# ST_LINK_V2-1.net
KiCad netlist of a schematic drawn in Altium Designer
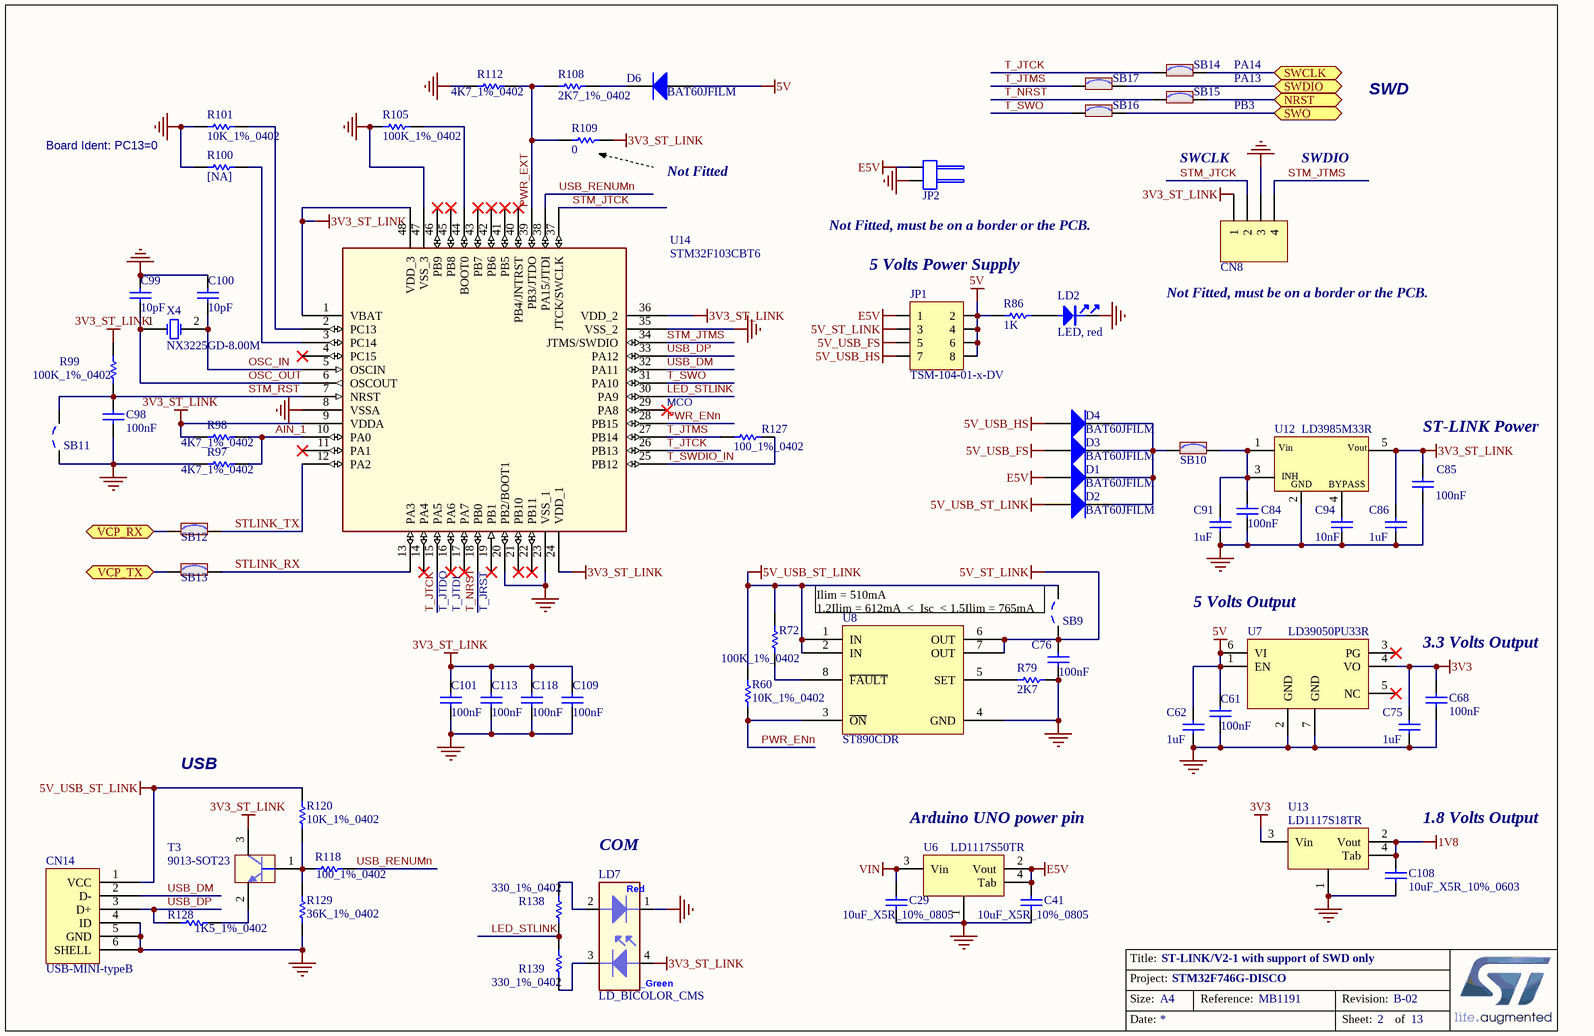
[diagram p0: ST_LINK_V2-1.SCHDOC]

(export (version "E")
  (design (tool "Eeschema 10.0.6"))
  (components
    (comp (ref "C29")
      (value "10uF_X5R_10%_0805")
      (footprint "0805C")
      (description "Capacitor,10uF,25V,X5R,10%,0805,YAGEO")
      (libsource (lib "MCD_TOOLS") (part "Cap_10uF_X5R_10%_0805"))
    )
    (comp (ref "C41")
      (value "10uF_X5R_10%_0805")
      (footprint "0805C")
      (description "Capacitor,10uF,25V,X5R,10%,0805,YAGEO")
      (libsource (lib "MCD_TOOLS") (part "Cap_10uF_X5R_10%_0805"))
    )
    (comp (ref "C61")
      (value "100nF")
      (footprint "0402C")
      (description "Capacitor,100nF,16V,X7R,10%,0402,YAGEO")
      (libsource (lib "MCD_TOOLS") (part "Cap_100nF_X7R_10%_0402"))
    )
    (comp (ref "C62")
      (value "1uF")
      (footprint "0603C")
      (description "Capacitor,1uF,16V,X5R,10%,0603,YAGEO")
      (libsource (lib "MCD_TOOLS") (part "Cap_1uF_X5R_10%_0603"))
    )
    (comp (ref "C68")
      (value "100nF")
      (footprint "0402C")
      (description "Capacitor,100nF,16V,X7R,10%,0402,YAGEO")
      (libsource (lib "MCD_TOOLS") (part "Cap_100nF_X7R_10%_0402"))
    )
    (comp (ref "C75")
      (value "1uF")
      (footprint "0603C")
      (description "Capacitor,1uF,16V,X5R,10%,0603,YAGEO")
      (libsource (lib "MCD_TOOLS") (part "Cap_1uF_X5R_10%_0603"))
    )
    (comp (ref "C76")
      (value "100nF")
      (footprint "0402C")
      (description "Capacitor,100nF,16V,X7R,10%,0402,YAGEO")
      (libsource (lib "MCD_TOOLS") (part "Cap_100nF_X7R_10%_0402"))
    )
    (comp (ref "C84")
      (value "100nF")
      (footprint "0402C")
      (description "Capacitor,100nF,16V,X7R,10%,0402,YAGEO")
      (libsource (lib "MCD_TOOLS") (part "Cap_100nF_X7R_10%_0402"))
    )
    (comp (ref "C85")
      (value "100nF")
      (footprint "0402C")
      (description "Capacitor,100nF,16V,X7R,10%,0402,YAGEO")
      (libsource (lib "MCD_TOOLS") (part "Cap_100nF_X7R_10%_0402"))
    )
    (comp (ref "C86")
      (value "1uF")
      (footprint "0603C")
      (description "Capacitor,1uF,16V,X5R,10%,0603,YAGEO")
      (libsource (lib "MCD_TOOLS") (part "Cap_1uF_X5R_10%_0603"))
    )
    (comp (ref "C91")
      (value "1uF")
      (footprint "0603C")
      (description "Capacitor,1uF,16V,X5R,10%,0603,YAGEO")
      (libsource (lib "MCD_TOOLS") (part "Cap_1uF_X5R_10%_0603"))
    )
    (comp (ref "C94")
      (value "10nF")
      (footprint "0603C")
      (description "Capacitor,10nF,50V,X7R,10%,0603,YAGEO")
      (libsource (lib "MCD_TOOLS") (part "Cap_10nF_X7R_10%_0603"))
    )
    (comp (ref "C98")
      (value "100nF")
      (footprint "0402C")
      (description "Capacitor,100nF,16V,X7R,10%,0402,YAGEO")
      (libsource (lib "MCD_TOOLS") (part "Cap_100nF_X7R_10%_0402"))
    )
    (comp (ref "C99")
      (value "10pF")
      (footprint "0402C")
      (description "Capacitor,10pF,50V,NPO,5%,0402,YAGEO")
      (libsource (lib "MCD_TOOLS") (part "Cap_10pF_NPO_5%_0402"))
    )
    (comp (ref "C100")
      (value "10pF")
      (footprint "0402C")
      (description "Capacitor,10pF,50V,NPO,5%,0402,YAGEO")
      (libsource (lib "MCD_TOOLS") (part "Cap_10pF_NPO_5%_0402"))
    )
    (comp (ref "C101")
      (value "100nF")
      (footprint "0402C")
      (description "Capacitor,100nF,16V,X7R,10%,0402,YAGEO")
      (libsource (lib "MCD_TOOLS") (part "Cap_100nF_X7R_10%_0402"))
    )
    (comp (ref "C108")
      (value "10uF_X5R_10%_0603")
      (footprint "0603C")
      (description "Capacitor,10uF,6.3V,X5R,10%,0603,YAGEO")
      (libsource (lib "MCD_TOOLS") (part "Cap_10uF_X5R_10%_0603"))
    )
    (comp (ref "C109")
      (value "100nF")
      (footprint "0402C")
      (description "Capacitor,100nF,16V,X7R,10%,0402,YAGEO")
      (libsource (lib "MCD_TOOLS") (part "Cap_100nF_X7R_10%_0402"))
    )
    (comp (ref "C113")
      (value "100nF")
      (footprint "0402C")
      (description "Capacitor,100nF,16V,X7R,10%,0402,YAGEO")
      (libsource (lib "MCD_TOOLS") (part "Cap_100nF_X7R_10%_0402"))
    )
    (comp (ref "C118")
      (value "100nF")
      (footprint "0402C")
      (description "Capacitor,100nF,16V,X7R,10%,0402,YAGEO")
      (libsource (lib "MCD_TOOLS") (part "Cap_100nF_X7R_10%_0402"))
    )
    (comp (ref "CN8")
      (value "Header 4")
      (footprint "Header 4")
      (description "Header, 4-Pin")
      (fields (field (name "PUBLISHER") "Altium Limited"))
      (libsource (lib "MCD_TOOLS") (part "Header 4"))
    )
    (comp (ref "CN14")
      (value "USB-MINI-typeB")
      (footprint "USB-MINI-B-SMD")
      (description "USB,MINI-USB-5P/F, 5075BMR-05-M")
      (libsource (lib "MCD_TOOLS") (part "USB-MINI-typeB connector"))
    )
    (comp (ref "D1")
      (value "BAT60JFILM")
      (footprint "SOD323/A")
      (libsource (lib "MCD_TOOLS") (part "BAT60JFILM"))
    )
    (comp (ref "D2")
      (value "BAT60JFILM")
      (footprint "SOD323/A")
      (libsource (lib "MCD_TOOLS") (part "BAT60JFILM"))
    )
    (comp (ref "D3")
      (value "BAT60JFILM")
      (footprint "SOD323/A")
      (libsource (lib "MCD_TOOLS") (part "BAT60JFILM"))
    )
    (comp (ref "D4")
      (value "BAT60JFILM")
      (footprint "SOD323/A")
      (libsource (lib "MCD_TOOLS") (part "BAT60JFILM"))
    )
    (comp (ref "D6")
      (value "BAT60JFILM")
      (footprint "SOD323/A")
      (libsource (lib "MCD_TOOLS") (part "BAT60JFILM"))
    )
    (comp (ref "JP1")
      (value "TSM-104-01-x-DV")
      (footprint "TSM-104-01-x-DV")
      (description "Header, 4-Pins, Double row Vertical, SMD, 2.54")
      (libsource (lib "MCD_TOOLS") (part "Header_4X2_SMD"))
    )
    (comp (ref "JP2")
      (value "TSM-102-01-x-SH")
      (footprint "SL_12_SMD_032_2")
      (description "Header, 2-Pins, Single row Horizontal SMD, 2.54")
      (libsource (lib "MCD_TOOLS") (part "JP2_CMS"))
    )
    (comp (ref "LD2")
      (value "LED, red")
      (footprint "0603D")
      (description "LED,red,0603,19-213-R6C-AP1Q2B/3T,everlight")
      (libsource (lib "MCD_TOOLS") (part "LED_red"))
    )
    (comp (ref "LD7")
      (value "LD_BICOLOR_CMS")
      (footprint "HSMF-A201")
      (description "Bicolor Led")
      (libsource (lib "MCD_TOOLS") (part "LD_BICOLOR_CMS"))
    )
    (comp (ref "R60")
      (value "10K_1%_0402")
      (footprint "0402R")
      (description "Resistor,10K,0402,1%,YAGEO")
      (libsource (lib "MCD_TOOLS") (part "Res_10K_1%_0402"))
    )
    (comp (ref "R72")
      (value "100K_1%_0402")
      (footprint "0402R")
      (description "Resistor,100K,0402,1%,YAGEO")
      (libsource (lib "MCD_TOOLS") (part "Res_100K_1%_0402"))
    )
    (comp (ref "R79")
      (value "2K7")
      (footprint "0402R")
      (description "Resistor,2K7,0402,1%,YAGEO")
      (libsource (lib "MCD_TOOLS") (part "Res_2K7_1%_0402"))
    )
    (comp (ref "R86")
      (value "1K")
      (footprint "0402R")
      (description "Resistor,1K,0402,1%,YAGEO")
      (libsource (lib "MCD_TOOLS") (part "Res_1K_1%_0402"))
    )
    (comp (ref "R97")
      (value "4K7_1%_0402")
      (footprint "0402R")
      (description "Resistor,4K7,0402,1%,YAGEO")
      (libsource (lib "MCD_TOOLS") (part "Res_4K7_1%_0402"))
    )
    (comp (ref "R98")
      (value "4K7_1%_0402")
      (footprint "0402R")
      (description "Resistor,4K7,0402,1%,YAGEO")
      (libsource (lib "MCD_TOOLS") (part "Res_4K7_1%_0402"))
    )
    (comp (ref "R99")
      (value "100K_1%_0402")
      (footprint "0402R")
      (description "Resistor,100K,0402,1%,YAGEO")
      (libsource (lib "MCD_TOOLS") (part "Res_100K_1%_0402"))
    )
    (comp (ref "R100")
      (value "[NA]")
      (footprint "0402R")
      (description "Resistor,[NA],0402")
      (libsource (lib "MCD_TOOLS") (part "Res_NA_0402"))
    )
    (comp (ref "R101")
      (value "10K_1%_0402")
      (footprint "0402R")
      (description "Resistor,10K,0402,1%,YAGEO")
      (libsource (lib "MCD_TOOLS") (part "Res_10K_1%_0402"))
    )
    (comp (ref "R105")
      (value "100K_1%_0402")
      (footprint "0402R")
      (description "Resistor,100K,0402,1%,YAGEO")
      (libsource (lib "MCD_TOOLS") (part "Res_100K_1%_0402"))
    )
    (comp (ref "R108")
      (value "2K7_1%_0402")
      (footprint "0402R")
      (description "Resistor,2K7,0402,1%,YAGEO")
      (libsource (lib "MCD_TOOLS") (part "Res_2K7_1%_0402"))
    )
    (comp (ref "R109")
      (value "0")
      (footprint "0402R")
      (description "Resistor,0,0402,5%,YAGEO")
      (libsource (lib "MCD_TOOLS") (part "Res_0_5%_0402"))
    )
    (comp (ref "R112")
      (value "4K7_1%_0402")
      (footprint "0402R")
      (description "Resistor,4K7,0402,1%,YAGEO")
      (libsource (lib "MCD_TOOLS") (part "Res_4K7_1%_0402"))
    )
    (comp (ref "R118")
      (value "100_1%_0402")
      (footprint "0402R")
      (description "Resistor,100,0402,1%,YAGEO")
      (libsource (lib "MCD_TOOLS") (part "Res_100_1%_0402"))
    )
    (comp (ref "R120")
      (value "10K_1%_0402")
      (footprint "0402R")
      (description "Resistor,10K,0402,1%,YAGEO")
      (libsource (lib "MCD_TOOLS") (part "Res_10K_1%_0402"))
    )
    (comp (ref "R127")
      (value "100_1%_0402")
      (footprint "0402R")
      (description "Resistor,100,0402,1%,YAGEO")
      (libsource (lib "MCD_TOOLS") (part "Res_100_1%_0402"))
    )
    (comp (ref "R128")
      (value "1K5_1%_0402")
      (footprint "0402R")
      (description "Resistor,1K5,0402,1%,YAGEO")
      (libsource (lib "MCD_TOOLS") (part "Res_1K5_1%_0402"))
    )
    (comp (ref "R129")
      (value "36K_1%_0402")
      (footprint "0402R")
      (description "Resistor,36K,0402,1%,YAGEO")
      (libsource (lib "MCD_TOOLS") (part "Res_36K_1%_0402"))
    )
    (comp (ref "R138")
      (value "330_1%_0402")
      (footprint "0402R")
      (description "Resistor,330,0402,1%,YAGEO")
      (libsource (lib "MCD_TOOLS") (part "Res_330_1%_0402"))
    )
    (comp (ref "R139")
      (value "330_1%_0402")
      (footprint "0402R")
      (description "Resistor,330,0402,1%,YAGEO")
      (libsource (lib "MCD_TOOLS") (part "Res_330_1%_0402"))
    )
    (comp (ref "SB9")
      (value "Solder Bridge OFF")
      (footprint "JP2_SMD")
      (libsource (lib "MCD_TOOLS") (part "SB_OFF"))
    )
    (comp (ref "SB10")
      (value "Solder Bridge ON")
      (footprint "JP2_SMD")
      (libsource (lib "MCD_TOOLS") (part "SB_ON"))
    )
    (comp (ref "SB11")
      (value "Solder Bridge OFF")
      (footprint "JP2_SMD")
      (libsource (lib "MCD_TOOLS") (part "SB_OFF"))
    )
    (comp (ref "SB12")
      (value "Solder Bridge ON")
      (footprint "JP2_SMD")
      (libsource (lib "MCD_TOOLS") (part "SB_ON"))
    )
    (comp (ref "SB13")
      (value "Solder Bridge ON")
      (footprint "JP2_SMD")
      (libsource (lib "MCD_TOOLS") (part "SB_ON"))
    )
    (comp (ref "SB14")
      (value "Solder Bridge ON")
      (footprint "JP2_SMD")
      (libsource (lib "MCD_TOOLS") (part "SB_ON"))
    )
    (comp (ref "SB15")
      (value "Solder Bridge ON")
      (footprint "JP2_SMD")
      (libsource (lib "MCD_TOOLS") (part "SB_ON"))
    )
    (comp (ref "SB16")
      (value "Solder Bridge ON")
      (footprint "JP2_SMD")
      (libsource (lib "MCD_TOOLS") (part "SB_ON"))
    )
    (comp (ref "SB17")
      (value "Solder Bridge ON")
      (footprint "JP2_SMD")
      (libsource (lib "MCD_TOOLS") (part "SB_ON"))
    )
    (comp (ref "T3")
      (value "9013-SOT23")
      (footprint "SOT23")
      (description "NPN Bipolar Transistor, SOT-23 Footprint")
      (libsource (lib "MCD_TOOLS") (part "9013-SOT23"))
    )
    (comp (ref "U6")
      (value "LD1117S50TR")
      (footprint "SOT-223")
      (description "IC REG LDO 5V 0.8A SOT223")
      (libsource (lib "MCD_TOOLS") (part "LD1117S50TR"))
    )
    (comp (ref "U7")
      (value "LD39050PU33R")
      (footprint "DFN6_3x3")
      (description "Ultra low drop-low , 500 mA low quiescent current")
      (libsource (lib "MCD_TOOLS") (part "LD39050P"))
    )
    (comp (ref "U8")
      (value "ST890CDR")
      (footprint "SO-8")
      (description "1.2 A current limited high-side power switch with thermal shutdown")
      (libsource (lib "MCD_TOOLS") (part "ST890CDR"))
    )
    (comp (ref "U12")
      (value "LD3985M33R")
      (footprint "SOT-23-5L")
      (description "Ultra low drop-low noise BiCMOS voltage, regulators low ESR capacitors compatible")
      (libsource (lib "MCD_TOOLS") (part "LD3985M33R"))
    )
    (comp (ref "U13")
      (value "LD1117S18TR")
      (footprint "SOT-223")
      (description "LOW DROP FIXED AND ADJUSTABLE POSITIVE VOLTAGE REGULATORS (1.8 Volts)")
      (libsource (lib "MCD_TOOLS") (part "LD1117S18TR"))
    )
    (comp (ref "U14")
      (value "STM32F103CBT6")
      (footprint "QFP48 7x7")
      (description "Medium-density performance line ARM-based 32-bit MCU with 128KB Flash")
      (libsource (lib "MCD_TOOLS") (part "STM32F103CBT6"))
    )
    (comp (ref "X4")
      (value "NX3225GD-8.00M")
      (footprint "XTAL_2SM_3R2X2R5")
      (description "Crystal 8Mhz, 8pF, -+50PPM, SMD")
      (libsource (lib "MCD_TOOLS") (part "XTAL_8M_NX3225GD"))
    )
  )
  (nets
    (net (code "1") (name "/AIN_1") (class "Default")
      (node (ref "R97") (pin "2") (pinfunction "2_2") (pintype "passive"))
      (node (ref "R98") (pin "2") (pinfunction "2_2") (pintype "passive"))
      (node (ref "U14") (pin "10") (pinfunction "PA0_10") (pintype "bidirectional"))
    )
    (net (code "2") (name "/LED_STLINK") (class "Default")
      (node (ref "R138") (pin "1") (pinfunction "1_1") (pintype "passive"))
      (node (ref "R139") (pin "2") (pinfunction "2_2") (pintype "passive"))
      (node (ref "U14") (pin "30") (pinfunction "PA9_30") (pintype "bidirectional"))
    )
    (net (code "3") (name "/NRST") (class "Default")
      (node (ref "SB15") (pin "2") (pinfunction "2_2") (pintype "passive"))
    )
    (net (code "4") (name "/OSC_IN") (class "Default")
      (node (ref "C100") (pin "2") (pinfunction "2_2") (pintype "passive"))
      (node (ref "U14") (pin "5") (pinfunction "OSCIN_5") (pintype "input"))
      (node (ref "X4") (pin "2") (pinfunction "OSC2_2") (pintype "passive"))
    )
    (net (code "5") (name "/OSC_OUT") (class "Default")
      (node (ref "C99") (pin "2") (pinfunction "2_2") (pintype "passive"))
      (node (ref "U14") (pin "6") (pinfunction "OSCOUT_6") (pintype "output"))
      (node (ref "X4") (pin "1") (pinfunction "OSC1_1") (pintype "passive"))
    )
    (net (code "6") (name "/PWR_ENn") (class "Default")
      (node (ref "R60") (pin "1") (pinfunction "1_1") (pintype "passive"))
      (node (ref "U14") (pin "28") (pinfunction "PB15_28") (pintype "bidirectional"))
      (node (ref "U8") (pin "3") (pinfunction "~{ON}_3") (pintype "passive"))
    )
    (net (code "7") (name "/PWR_EXT") (class "Default")
      (node (ref "R108") (pin "1") (pinfunction "1_1") (pintype "passive"))
      (node (ref "R109") (pin "1") (pinfunction "1_1") (pintype "passive"))
      (node (ref "R112") (pin "2") (pinfunction "2_2") (pintype "passive"))
      (node (ref "U14") (pin "39") (pinfunction "PB3/JTDO_39") (pintype "bidirectional"))
    )
    (net (code "8") (name "/STLINK_RX") (class "Default")
      (node (ref "SB13") (pin "2") (pinfunction "2_2") (pintype "passive"))
      (node (ref "U14") (pin "13") (pinfunction "PA3_13") (pintype "bidirectional"))
    )
    (net (code "9") (name "/STLINK_TX") (class "Default")
      (node (ref "SB12") (pin "2") (pinfunction "2_2") (pintype "passive"))
      (node (ref "U14") (pin "12") (pinfunction "PA2_12") (pintype "bidirectional"))
    )
    (net (code "10") (name "/STM_JTCK") (class "Default")
      (node (ref "CN8") (pin "2") (pinfunction "2_2") (pintype "passive"))
      (node (ref "U14") (pin "37") (pinfunction "JTCK/SWCLK_37") (pintype "bidirectional"))
    )
    (net (code "11") (name "/STM_JTMS") (class "Default")
      (node (ref "CN8") (pin "4") (pinfunction "4_4") (pintype "passive"))
      (node (ref "U14") (pin "34") (pinfunction "JTMS/SWDIO_34") (pintype "bidirectional"))
    )
    (net (code "12") (name "/STM_RST") (class "Default")
      (node (ref "C98") (pin "2") (pinfunction "2_2") (pintype "passive"))
      (node (ref "R99") (pin "1") (pinfunction "1_1") (pintype "passive"))
      (node (ref "SB11") (pin "2") (pinfunction "2_2") (pintype "passive"))
      (node (ref "U14") (pin "7") (pinfunction "NRST_7") (pintype "input"))
    )
    (net (code "13") (name "/SWCLK") (class "Default")
      (node (ref "SB14") (pin "2") (pinfunction "2_2") (pintype "passive"))
    )
    (net (code "14") (name "/SWDIO") (class "Default")
      (node (ref "SB17") (pin "2") (pinfunction "2_2") (pintype "passive"))
    )
    (net (code "15") (name "/SWO") (class "Default")
      (node (ref "SB16") (pin "2") (pinfunction "2_2") (pintype "passive"))
    )
    (net (code "16") (name "/T_JTCK") (class "Default")
      (node (ref "SB14") (pin "1") (pinfunction "1_1") (pintype "passive"))
      (node (ref "U14") (pin "15") (pinfunction "PA5_15") (pintype "bidirectional"))
      (node (ref "U14") (pin "26") (pinfunction "PB13_26") (pintype "bidirectional"))
    )
    (net (code "17") (name "/T_JTMS") (class "Default")
      (node (ref "R127") (pin "1") (pinfunction "1_1") (pintype "passive"))
      (node (ref "SB17") (pin "1") (pinfunction "1_1") (pintype "passive"))
      (node (ref "U14") (pin "27") (pinfunction "PB14_27") (pintype "bidirectional"))
    )
    (net (code "18") (name "/T_NRST") (class "Default")
      (node (ref "SB15") (pin "1") (pinfunction "1_1") (pintype "passive"))
      (node (ref "U14") (pin "18") (pinfunction "PB0_18") (pintype "bidirectional"))
    )
    (net (code "19") (name "/T_SWDIO_IN") (class "Default")
      (node (ref "R127") (pin "2") (pinfunction "2_2") (pintype "passive"))
      (node (ref "U14") (pin "25") (pinfunction "PB12_25") (pintype "bidirectional"))
    )
    (net (code "20") (name "/T_SWO") (class "Default")
      (node (ref "SB16") (pin "1") (pinfunction "1_1") (pintype "passive"))
      (node (ref "U14") (pin "31") (pinfunction "PA10_31") (pintype "bidirectional"))
    )
    (net (code "21") (name "/USB_DM") (class "Default")
      (node (ref "CN14") (pin "2") (pinfunction "D-_2") (pintype "passive"))
      (node (ref "U14") (pin "32") (pinfunction "PA11_32") (pintype "bidirectional"))
    )
    (net (code "22") (name "/USB_DP") (class "Default")
      (node (ref "CN14") (pin "3") (pinfunction "D+_3") (pintype "passive"))
      (node (ref "R128") (pin "1") (pinfunction "1_1") (pintype "passive"))
      (node (ref "U14") (pin "33") (pinfunction "PA12_33") (pintype "bidirectional"))
    )
    (net (code "23") (name "/USB_RENUMn") (class "Default")
      (node (ref "R118") (pin "2") (pinfunction "2_2") (pintype "passive"))
      (node (ref "U14") (pin "38") (pinfunction "PA15/JTDI_38") (pintype "bidirectional"))
    )
    (net (code "24") (name "/VCP_RX") (class "Default")
      (node (ref "SB12") (pin "1") (pinfunction "1_1") (pintype "passive"))
    )
    (net (code "25") (name "/VCP_TX") (class "Default")
      (node (ref "SB13") (pin "1") (pinfunction "1_1") (pintype "passive"))
    )
    (net (code "26") (name "1V8") (class "Default")
      (node (ref "C108") (pin "2") (pinfunction "2_2") (pintype "passive"))
      (node (ref "U13") (pin "2") (pinfunction "Vout_2") (pintype "passive"))
      (node (ref "U13") (pin "4") (pinfunction "Tab_4") (pintype "passive"))
    )
    (net (code "27") (name "3V3") (class "Default")
      (node (ref "C68") (pin "2") (pinfunction "2_2") (pintype "passive"))
      (node (ref "C75") (pin "2") (pinfunction "2_2") (pintype "passive"))
      (node (ref "U13") (pin "3") (pinfunction "Vin_3") (pintype "passive"))
      (node (ref "U7") (pin "4") (pinfunction "VO_4") (pintype "passive"))
    )
    (net (code "28") (name "3V3_ST_LINK") (class "Default")
      (node (ref "C101") (pin "2") (pinfunction "2_2") (pintype "passive"))
      (node (ref "C109") (pin "2") (pinfunction "2_2") (pintype "passive"))
      (node (ref "C113") (pin "2") (pinfunction "2_2") (pintype "passive"))
      (node (ref "C118") (pin "1") (pinfunction "1_1") (pintype "passive"))
      (node (ref "C85") (pin "2") (pinfunction "2_2") (pintype "passive"))
      (node (ref "C86") (pin "1") (pinfunction "1_1") (pintype "passive"))
      (node (ref "CN8") (pin "1") (pinfunction "1_1") (pintype "passive"))
      (node (ref "LD7") (pin "4") (pinfunction "4_4") (pintype "passive"))
      (node (ref "R109") (pin "2") (pinfunction "2_2") (pintype "passive"))
      (node (ref "R98") (pin "1") (pinfunction "1_1") (pintype "passive"))
      (node (ref "R99") (pin "2") (pinfunction "2_2") (pintype "passive"))
      (node (ref "T3") (pin "3") (pinfunction "C_3") (pintype "passive"))
      (node (ref "U12") (pin "5") (pinfunction "Vout_5") (pintype "passive"))
      (node (ref "U14") (pin "1") (pinfunction "VBAT_1") (pintype "power_in"))
      (node (ref "U14") (pin "24") (pinfunction "VDD_1_24") (pintype "power_in"))
      (node (ref "U14") (pin "36") (pinfunction "VDD_2_36") (pintype "power_in"))
      (node (ref "U14") (pin "48") (pinfunction "VDD_3_48") (pintype "power_in"))
      (node (ref "U14") (pin "9") (pinfunction "VDDA_9") (pintype "power_in"))
    )
    (net (code "29") (name "5V") (class "Default")
      (node (ref "C61") (pin "2") (pinfunction "2_2") (pintype "passive"))
      (node (ref "C62") (pin "2") (pinfunction "2_2") (pintype "passive"))
      (node (ref "D6") (pin "1") (pinfunction "A_1") (pintype "passive"))
      (node (ref "JP1") (pin "2") (pinfunction "2_2") (pintype "passive"))
      (node (ref "JP1") (pin "4") (pinfunction "4_4") (pintype "passive"))
      (node (ref "JP1") (pin "6") (pinfunction "6_6") (pintype "passive"))
      (node (ref "JP1") (pin "8") (pinfunction "8_8") (pintype "passive"))
      (node (ref "R86") (pin "1") (pinfunction "1_1") (pintype "passive"))
      (node (ref "U7") (pin "1") (pinfunction "EN_1") (pintype "passive"))
      (node (ref "U7") (pin "6") (pinfunction "VI_6") (pintype "passive"))
    )
    (net (code "30") (name "5V_ST_LINK") (class "Default")
      (node (ref "C76") (pin "2") (pinfunction "2_2") (pintype "passive"))
      (node (ref "JP1") (pin "3") (pinfunction "3_3") (pintype "passive"))
      (node (ref "SB9") (pin "1") (pinfunction "1_1") (pintype "passive"))
      (node (ref "U8") (pin "6") (pinfunction "OUT_6") (pintype "passive"))
      (node (ref "U8") (pin "7") (pinfunction "OUT_7") (pintype "passive"))
    )
    (net (code "31") (name "5V_USB_FS") (class "Default")
      (node (ref "D3") (pin "1") (pinfunction "A_1") (pintype "passive"))
      (node (ref "JP1") (pin "5") (pinfunction "5_5") (pintype "passive"))
    )
    (net (code "32") (name "5V_USB_HS") (class "Default")
      (node (ref "D4") (pin "1") (pinfunction "A_1") (pintype "passive"))
      (node (ref "JP1") (pin "7") (pinfunction "7_7") (pintype "passive"))
    )
    (net (code "33") (name "5V_USB_ST_LINK") (class "Default")
      (node (ref "CN14") (pin "1") (pinfunction "VCC_1") (pintype "power_in"))
      (node (ref "D2") (pin "1") (pinfunction "A_1") (pintype "passive"))
      (node (ref "R120") (pin "2") (pinfunction "2_2") (pintype "passive"))
      (node (ref "R60") (pin "2") (pinfunction "2_2") (pintype "passive"))
      (node (ref "R72") (pin "2") (pinfunction "2_2") (pintype "passive"))
      (node (ref "SB9") (pin "2") (pinfunction "2_2") (pintype "passive"))
      (node (ref "U8") (pin "1") (pinfunction "IN_1") (pintype "passive"))
      (node (ref "U8") (pin "2") (pinfunction "IN_2") (pintype "passive"))
    )
    (net (code "34") (name "E5V") (class "Default")
      (node (ref "C41") (pin "2") (pinfunction "2_2") (pintype "passive"))
      (node (ref "D1") (pin "1") (pinfunction "A_1") (pintype "passive"))
      (node (ref "JP1") (pin "1") (pinfunction "1_1") (pintype "passive"))
      (node (ref "JP2") (pin "1") (pinfunction "COMMON_1") (pintype "passive"))
      (node (ref "U6") (pin "2") (pinfunction "Vout_2") (pintype "passive"))
      (node (ref "U6") (pin "4") (pinfunction "Tab_4") (pintype "passive"))
    )
    (net (code "35") (name "GND") (class "Default")
      (node (ref "C100") (pin "1") (pinfunction "1_1") (pintype "passive"))
      (node (ref "C101") (pin "1") (pinfunction "1_1") (pintype "passive"))
      (node (ref "C108") (pin "1") (pinfunction "1_1") (pintype "passive"))
      (node (ref "C109") (pin "1") (pinfunction "1_1") (pintype "passive"))
      (node (ref "C113") (pin "1") (pinfunction "1_1") (pintype "passive"))
      (node (ref "C118") (pin "2") (pinfunction "2_2") (pintype "passive"))
      (node (ref "C29") (pin "1") (pinfunction "1_1") (pintype "passive"))
      (node (ref "C41") (pin "1") (pinfunction "1_1") (pintype "passive"))
      (node (ref "C61") (pin "1") (pinfunction "1_1") (pintype "passive"))
      (node (ref "C62") (pin "1") (pinfunction "1_1") (pintype "passive"))
      (node (ref "C68") (pin "1") (pinfunction "1_1") (pintype "passive"))
      (node (ref "C75") (pin "1") (pinfunction "1_1") (pintype "passive"))
      (node (ref "C76") (pin "1") (pinfunction "1_1") (pintype "passive"))
      (node (ref "C84") (pin "1") (pinfunction "1_1") (pintype "passive"))
      (node (ref "C85") (pin "1") (pinfunction "1_1") (pintype "passive"))
      (node (ref "C86") (pin "2") (pinfunction "2_2") (pintype "passive"))
      (node (ref "C91") (pin "1") (pinfunction "1_1") (pintype "passive"))
      (node (ref "C94") (pin "1") (pinfunction "1_1") (pintype "passive"))
      (node (ref "C98") (pin "1") (pinfunction "1_1") (pintype "passive"))
      (node (ref "C99") (pin "1") (pinfunction "1_1") (pintype "passive"))
      (node (ref "CN14") (pin "4") (pinfunction "ID_4") (pintype "passive"))
      (node (ref "CN14") (pin "5") (pinfunction "GND_5") (pintype "passive"))
      (node (ref "CN14") (pin "6") (pinfunction "SHELL_6") (pintype "passive"))
      (node (ref "CN8") (pin "3") (pinfunction "3_3") (pintype "passive"))
      (node (ref "JP2") (pin "2") (pinfunction "NO_2") (pintype "passive"))
      (node (ref "LD2") (pin "2") (pintype "passive"))
      (node (ref "LD7") (pin "1") (pinfunction "1_1") (pintype "passive"))
      (node (ref "R100") (pin "1") (pinfunction "1_1") (pintype "passive"))
      (node (ref "R101") (pin "1") (pinfunction "1_1") (pintype "passive"))
      (node (ref "R105") (pin "1") (pinfunction "1_1") (pintype "passive"))
      (node (ref "R112") (pin "1") (pinfunction "1_1") (pintype "passive"))
      (node (ref "R129") (pin "1") (pinfunction "1_1") (pintype "passive"))
      (node (ref "R79") (pin "2") (pinfunction "2_2") (pintype "passive"))
      (node (ref "R97") (pin "1") (pinfunction "1_1") (pintype "passive"))
      (node (ref "SB11") (pin "1") (pinfunction "1_1") (pintype "passive"))
      (node (ref "U12") (pin "2") (pinfunction "GND_2") (pintype "passive"))
      (node (ref "U13") (pin "1") (pintype "passive"))
      (node (ref "U14") (pin "20") (pinfunction "PB2/BOOT1_20") (pintype "bidirectional"))
      (node (ref "U14") (pin "23") (pinfunction "VSS_1_23") (pintype "power_in"))
      (node (ref "U14") (pin "35") (pinfunction "VSS_2_35") (pintype "power_in"))
      (node (ref "U14") (pin "47") (pinfunction "VSS_3_47") (pintype "power_in"))
      (node (ref "U14") (pin "8") (pinfunction "VSSA_8") (pintype "power_in"))
      (node (ref "U6") (pin "1") (pintype "passive"))
      (node (ref "U7") (pin "2") (pinfunction "GND_2") (pintype "passive"))
      (node (ref "U7") (pin "7") (pinfunction "GND_7") (pintype "passive"))
      (node (ref "U8") (pin "4") (pinfunction "GND_4") (pintype "passive"))
    )
    (net (code "36") (name "Net-(D1-K)") (class "Default")
      (node (ref "D1") (pin "2") (pinfunction "K_2") (pintype "passive"))
      (node (ref "D2") (pin "2") (pinfunction "K_2") (pintype "passive"))
      (node (ref "D3") (pin "2") (pinfunction "K_2") (pintype "passive"))
      (node (ref "D4") (pin "2") (pinfunction "K_2") (pintype "passive"))
      (node (ref "SB10") (pin "1") (pinfunction "1_1") (pintype "passive"))
    )
    (net (code "37") (name "Net-(D6-K)") (class "Default")
      (node (ref "D6") (pin "2") (pinfunction "K_2") (pintype "passive"))
      (node (ref "R108") (pin "2") (pinfunction "2_2") (pintype "passive"))
    )
    (net (code "38") (name "Net-(LD2-Pad1)") (class "Default")
      (node (ref "LD2") (pin "1") (pintype "passive"))
      (node (ref "R86") (pin "2") (pinfunction "2_2") (pintype "passive"))
    )
    (net (code "39") (name "Net-(LD7-Pad2)") (class "Default")
      (node (ref "LD7") (pin "2") (pinfunction "2_2") (pintype "passive"))
      (node (ref "R138") (pin "2") (pinfunction "2_2") (pintype "passive"))
    )
    (net (code "40") (name "Net-(LD7-Pad3)") (class "Default")
      (node (ref "LD7") (pin "3") (pinfunction "3_3") (pintype "passive"))
      (node (ref "R139") (pin "1") (pinfunction "1_1") (pintype "passive"))
    )
    (net (code "41") (name "Net-(T3-B)") (class "Default")
      (node (ref "R118") (pin "1") (pinfunction "1_1") (pintype "passive"))
      (node (ref "R120") (pin "1") (pinfunction "1_1") (pintype "passive"))
      (node (ref "R129") (pin "2") (pinfunction "2_2") (pintype "passive"))
      (node (ref "T3") (pin "1") (pinfunction "B_1") (pintype "passive"))
    )
    (net (code "42") (name "Net-(T3-E)") (class "Default")
      (node (ref "R128") (pin "2") (pinfunction "2_2") (pintype "passive"))
      (node (ref "T3") (pin "2") (pinfunction "E_2") (pintype "passive"))
    )
    (net (code "43") (name "Net-(U8-SET)") (class "Default")
      (node (ref "R79") (pin "1") (pinfunction "1_1") (pintype "passive"))
      (node (ref "U8") (pin "5") (pinfunction "SET_5") (pintype "passive"))
    )
    (net (code "44") (name "Net-(U8-~{FAULT})") (class "Default")
      (node (ref "R72") (pin "1") (pinfunction "1_1") (pintype "passive"))
      (node (ref "U8") (pin "8") (pinfunction "~{FAULT}_8") (pintype "passive"))
    )
    (net (code "45") (name "Net-(U12-BYPASS)") (class "Default")
      (node (ref "C94") (pin "2") (pinfunction "2_2") (pintype "passive"))
      (node (ref "U12") (pin "4") (pinfunction "BYPASS_4") (pintype "passive"))
    )
    (net (code "46") (name "Net-(U12-CE)") (class "Default")
      (node (ref "C84") (pin "2") (pinfunction "2_2") (pintype "passive"))
      (node (ref "C91") (pin "2") (pinfunction "2_2") (pintype "passive"))
      (node (ref "SB10") (pin "2") (pinfunction "2_2") (pintype "passive"))
      (node (ref "U12") (pin "1") (pinfunction "Vin_1") (pintype "passive"))
      (node (ref "U12") (pin "3") (pinfunction "CE_3") (pintype "passive"))
    )
    (net (code "47") (name "Net-(U14-BOOT0)") (class "Default")
      (node (ref "R105") (pin "2") (pinfunction "2_2") (pintype "passive"))
      (node (ref "U14") (pin "44") (pinfunction "BOOT0_44") (pintype "bidirectional"))
    )
    (net (code "48") (name "Net-(U14-PC13)") (class "Default")
      (node (ref "R101") (pin "2") (pinfunction "2_2") (pintype "passive"))
      (node (ref "U14") (pin "2") (pinfunction "PC13_2") (pintype "bidirectional"))
    )
    (net (code "49") (name "Net-(U14-PC14)") (class "Default")
      (node (ref "R100") (pin "2") (pinfunction "2_2") (pintype "passive"))
      (node (ref "U14") (pin "3") (pinfunction "PC14_3") (pintype "bidirectional"))
    )
    (net (code "50") (name "VIN") (class "Default")
      (node (ref "C29") (pin "2") (pinfunction "2_2") (pintype "passive"))
      (node (ref "U6") (pin "3") (pinfunction "Vin_3") (pintype "passive"))
    )
    (net (code "51") (name "unconnected-(U7-NC-Pad5)") (class "Default")
      (node (ref "U7") (pin "5") (pinfunction "NC_5") (pintype "passive+no_connect"))
    )
    (net (code "52") (name "unconnected-(U7-PG-Pad3)") (class "Default")
      (node (ref "U7") (pin "3") (pinfunction "PG_3") (pintype "passive+no_connect"))
    )
    (net (code "53") (name "unconnected-(U14-PA1-Pad11)") (class "Default")
      (node (ref "U14") (pin "11") (pinfunction "PA1_11") (pintype "bidirectional+no_connect"))
    )
    (net (code "54") (name "unconnected-(U14-PA4-Pad14)") (class "Default")
      (node (ref "U14") (pin "14") (pinfunction "PA4_14") (pintype "bidirectional+no_connect"))
    )
    (net (code "55") (name "unconnected-(U14-PA6-Pad16)") (class "Default")
      (node (ref "U14") (pin "16") (pinfunction "PA6_16") (pintype "bidirectional+no_connect"))
    )
    (net (code "56") (name "unconnected-(U14-PA7-Pad17)") (class "Default")
      (node (ref "U14") (pin "17") (pinfunction "PA7_17") (pintype "bidirectional+no_connect"))
    )
    (net (code "57") (name "unconnected-(U14-PA8-Pad29)") (class "Default")
      (node (ref "U14") (pin "29") (pinfunction "PA8_29") (pintype "bidirectional+no_connect"))
    )
    (net (code "58") (name "unconnected-(U14-PB1-Pad19)") (class "Default")
      (node (ref "U14") (pin "19") (pinfunction "PB1_19") (pintype "input+no_connect"))
    )
    (net (code "59") (name "unconnected-(U14-PB4{slash}JNTRST-Pad40)") (class "Default")
      (node (ref "U14") (pin "40") (pinfunction "PB4/JNTRST_40") (pintype "bidirectional+no_connect"))
    )
    (net (code "60") (name "unconnected-(U14-PB5-Pad41)") (class "Default")
      (node (ref "U14") (pin "41") (pinfunction "PB5_41") (pintype "bidirectional+no_connect"))
    )
    (net (code "61") (name "unconnected-(U14-PB6-Pad42)") (class "Default")
      (node (ref "U14") (pin "42") (pinfunction "PB6_42") (pintype "bidirectional+no_connect"))
    )
    (net (code "62") (name "unconnected-(U14-PB7-Pad43)") (class "Default")
      (node (ref "U14") (pin "43") (pinfunction "PB7_43") (pintype "bidirectional+no_connect"))
    )
    (net (code "63") (name "unconnected-(U14-PB8-Pad45)") (class "Default")
      (node (ref "U14") (pin "45") (pinfunction "PB8_45") (pintype "bidirectional+no_connect"))
    )
    (net (code "64") (name "unconnected-(U14-PB9-Pad46)") (class "Default")
      (node (ref "U14") (pin "46") (pinfunction "PB9_46") (pintype "bidirectional+no_connect"))
    )
    (net (code "65") (name "unconnected-(U14-PB10-Pad21)") (class "Default")
      (node (ref "U14") (pin "21") (pinfunction "PB10_21") (pintype "bidirectional+no_connect"))
    )
    (net (code "66") (name "unconnected-(U14-PB11-Pad22)") (class "Default")
      (node (ref "U14") (pin "22") (pinfunction "PB11_22") (pintype "bidirectional+no_connect"))
    )
    (net (code "67") (name "unconnected-(U14-PC15-Pad4)") (class "Default")
      (node (ref "U14") (pin "4") (pinfunction "PC15_4") (pintype "bidirectional+no_connect"))
    )
  )
)
